# I2C_RTC_DS3231.net
KiCad netlist of a schematic drawn in Altium Designer
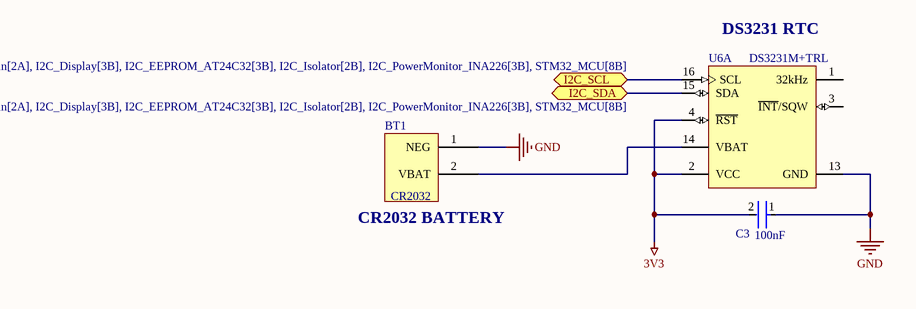
[diagram p0: I2C_RTC_DS3231.SchDoc]

(export (version "E")
  (design (tool "Eeschema 10.0.6"))
  (components
    (comp (ref "BT1")
      (value "CR2032_HOLDER_TH")
      (footprint "CR2032_HOLDER_TH")
      (libsource (lib "CR2032_HOLDER_TH") (part "CR2032_HOLDER_TH"))
    )
    (comp (ref "C3")
      (value "100nF")
      (footprint "FP-CGA3E-0_3-0_1-IPC_A")
      (description "Cap Ceramic 100nF 50V X7R 10% Pad SMD 0603 +125°C Automotive T/R")
      (fields (field (name "TOLERANCE") "10%") (field (name "VOLTAGE") "50V"))
      (libsource (lib "Altium Content Vault") (part "b4654b650e69147ec39a6b967a45e02"))
    )
    (comp (ref "U6")
      (value "DS3231M+TRL")
      (footprint "W16MK+1_N")
      (description "+/-5ppm, MEMS based Real-Time Clock, I2C Interface, 16-Pin SO, -40 to 85 degC, Pb-Free, Reel")
      (libsource (lib "Altium Content Vault") (part "PR-RTC-DS3231M-IL16"))
    )
  )
  (nets
    (net (code "1") (name "/I2C_SCL") (class "Default")
      (node (ref "U6") (pin "16") (pinfunction "SCL_16") (pintype "input"))
    )
    (net (code "2") (name "/I2C_SDA") (class "Default")
      (node (ref "U6") (pin "15") (pinfunction "SDA_15") (pintype "bidirectional"))
    )
    (net (code "3") (name "3V3") (class "Default")
      (node (ref "C3") (pin "2") (pinfunction "2_2") (pintype "passive"))
      (node (ref "U6") (pin "2") (pinfunction "VCC_2") (pintype "power_in"))
      (node (ref "U6") (pin "4") (pinfunction "~{RST}_4") (pintype "bidirectional"))
    )
    (net (code "4") (name "GND") (class "Default")
      (node (ref "BT1") (pin "1") (pinfunction "NEG_1") (pintype "passive"))
      (node (ref "C3") (pin "1") (pinfunction "1_1") (pintype "passive"))
      (node (ref "U6") (pin "13") (pinfunction "GND_13") (pintype "power_in"))
    )
    (net (code "5") (name "Net-(BT1-VBAT)") (class "Default")
      (node (ref "BT1") (pin "2") (pinfunction "VBAT_2") (pintype "passive"))
      (node (ref "U6") (pin "14") (pinfunction "VBAT_14") (pintype "power_in"))
    )
    (net (code "6") (name "unconnected-(U6A-32kHz-Pad1)") (class "Default")
      (node (ref "U6") (pin "1") (pinfunction "32kHz_1") (pintype "open_collector"))
    )
    (net (code "7") (name "unconnected-(U6A-~{INT}{slash}SQW-Pad3)") (class "Default")
      (node (ref "U6") (pin "3") (pinfunction "~{INT}/SQW_3") (pintype "bidirectional"))
    )
  )
)
